# wk3Schematic.net
KiCad netlist of a schematic drawn in EAGLE
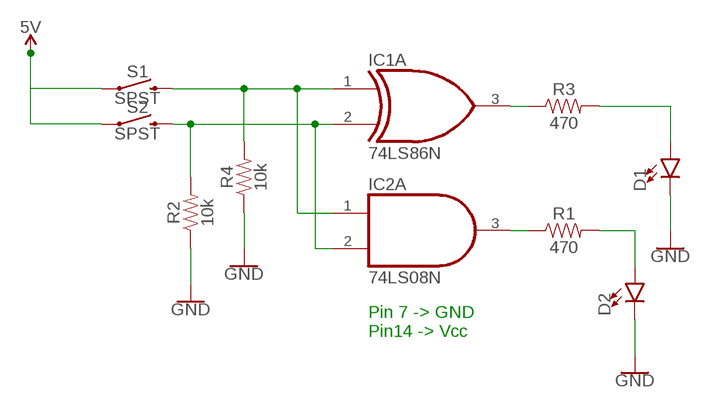
[diagram p0: schematic, sheet 1]

(export (version "E")
  (design (tool "Eeschema 10.0.6"))
  (components
    (comp (ref "D1")
      (value "LED5MM")
      (footprint "eagle-import:LED_5MM")
      (libsource (lib "eagle-import") (part "LED5MM"))
    )
    (comp (ref "D2")
      (value "LED5MM")
      (footprint "eagle-import:LED_5MM")
      (libsource (lib "eagle-import") (part "LED5MM"))
    )
    (comp (ref "IC1")
      (value "74LS86N")
      (footprint "eagle-import:DIL14")
      (libsource (lib "eagle-import") (part "7486NLS"))
    )
    (comp (ref "IC2")
      (value "74LS08N")
      (footprint "eagle-import:DIL14")
      (libsource (lib "eagle-import") (part "7408NLS"))
    )
    (comp (ref "R1")
      (value "470")
      (footprint "eagle-import:AXIAL-0.3")
      (libsource (lib "eagle-import") (part "10KOHM-HORIZ-1/4W-1%"))
    )
    (comp (ref "R2")
      (value "10k")
      (footprint "eagle-import:AXIAL-0.3")
      (libsource (lib "eagle-import") (part "10KOHM-HORIZ-1/4W-1%"))
    )
    (comp (ref "R3")
      (value "470")
      (footprint "eagle-import:AXIAL-0.3")
      (libsource (lib "eagle-import") (part "10KOHM-HORIZ-1/4W-1%"))
    )
    (comp (ref "R4")
      (value "10k")
      (footprint "eagle-import:AXIAL-0.3")
      (libsource (lib "eagle-import") (part "10KOHM-HORIZ-1/4W-1%"))
    )
    (comp (ref "S1")
      (value "SPST")
      (footprint "eagle-import:TACTILE_SWITCH_PTH_12MM")
      (libsource (lib "eagle-import") (part "MOMENTARY-SWITCH-SPST-PTH-12MM"))
    )
    (comp (ref "S2")
      (value "SPST")
      (footprint "eagle-import:TACTILE_SWITCH_PTH_12MM")
      (libsource (lib "eagle-import") (part "MOMENTARY-SWITCH-SPST-PTH-12MM"))
    )
  )
  (nets
    (net (code "1") (name "5V") (class "Default")
      (node (ref "S1") (pin "1") (pinfunction "1_1") (pintype "passive"))
      (node (ref "S2") (pin "1") (pinfunction "1_1") (pintype "passive"))
    )
    (net (code "2") (name "GND") (class "Default")
      (node (ref "D1") (pin "K") (pinfunction "C_K") (pintype "passive"))
      (node (ref "D2") (pin "K") (pinfunction "C_K") (pintype "passive"))
      (node (ref "R2") (pin "P$1") (pinfunction "1_P$1") (pintype "passive"))
      (node (ref "R4") (pin "P$1") (pinfunction "1_P$1") (pintype "passive"))
    )
    (net (code "3") (name "Net-(IC1A-I0)") (class "Default")
      (node (ref "IC1") (pin "1") (pinfunction "I0_1") (pintype "input"))
      (node (ref "IC2") (pin "1") (pinfunction "I0_1") (pintype "input"))
      (node (ref "R4") (pin "P$2") (pinfunction "2_P$2") (pintype "passive"))
      (node (ref "S1") (pin "3") (pinfunction "2_3") (pintype "passive"))
    )
    (net (code "4") (name "Net-(IC1A-I1)") (class "Default")
      (node (ref "IC1") (pin "2") (pinfunction "I1_2") (pintype "input"))
      (node (ref "IC2") (pin "2") (pinfunction "I1_2") (pintype "input"))
      (node (ref "R2") (pin "P$2") (pinfunction "2_P$2") (pintype "passive"))
      (node (ref "S2") (pin "3") (pinfunction "2_3") (pintype "passive"))
    )
    (net (code "5") (name "Net-(IC1A-O)") (class "Default")
      (node (ref "IC1") (pin "3") (pinfunction "O_3") (pintype "output"))
      (node (ref "R3") (pin "P$1") (pinfunction "1_P$1") (pintype "passive"))
    )
    (net (code "6") (name "Net-(IC2A-O)") (class "Default")
      (node (ref "IC2") (pin "3") (pinfunction "O_3") (pintype "output"))
      (node (ref "R1") (pin "P$1") (pinfunction "1_P$1") (pintype "passive"))
    )
    (net (code "7") (name "Net-(R1-2)") (class "Default")
      (node (ref "D2") (pin "A") (pinfunction "A_A") (pintype "passive"))
      (node (ref "R1") (pin "P$2") (pinfunction "2_P$2") (pintype "passive"))
    )
    (net (code "8") (name "Net-(R3-2)") (class "Default")
      (node (ref "D1") (pin "A") (pinfunction "A_A") (pintype "passive"))
      (node (ref "R3") (pin "P$2") (pinfunction "2_P$2") (pintype "passive"))
    )
  )
)
